# Mode_V1.net
KiCad netlist of a schematic drawn in Altium Designer
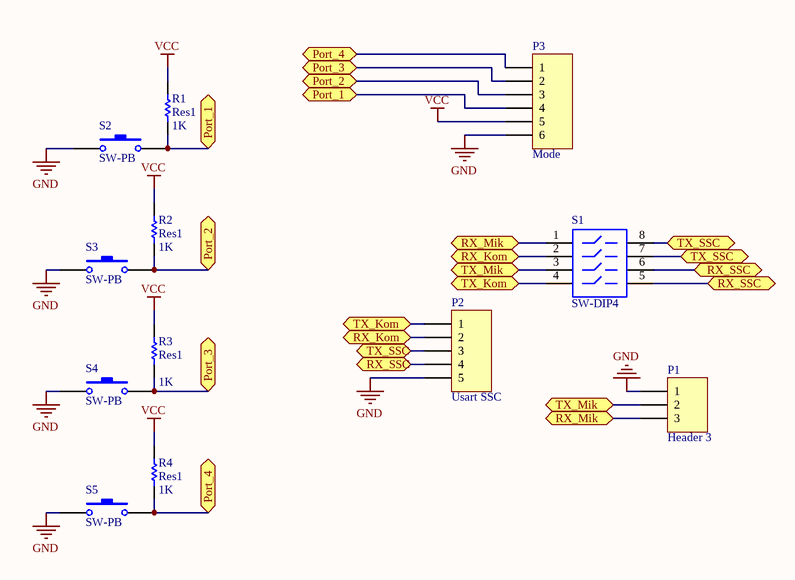
[diagram p0: Mode_V1.SchDoc]

(export (version "E")
  (design (tool "Eeschema 10.0.6"))
  (components
    (comp (ref "P1")
      (value "Header 3")
      (footprint "HDR1X3")
      (description "Header, 3-Pin")
      (fields (field (name "PUBLISHER") "Altium Limited"))
      (libsource (lib "Miscellaneous Connectors") (part "Header 3"))
    )
    (comp (ref "P2")
      (value "Usart SSC")
      (footprint "HDR1X5")
      (description "Header, 5-Pin")
      (fields (field (name "PUBLISHER") "Altium Limited"))
      (libsource (lib "Miscellaneous Connectors") (part "Header 5"))
    )
    (comp (ref "P3")
      (value "Mode")
      (footprint "HDR1X6")
      (description "Header, 6-Pin")
      (fields (field (name "PUBLISHER") "Altium Limited"))
      (libsource (lib "Miscellaneous Connectors") (part "Header 6"))
    )
    (comp (ref "R1")
      (value "Res1")
      (footprint "AXIAL-0.3")
      (description "Resistor")
      (fields (field (name "ALTIUM_VALUE") "1K") (field (name "PUBLISHER") "Altium Limited"))
      (libsource (lib "Miscellaneous Devices") (part "Res1"))
    )
    (comp (ref "R2")
      (value "Res1")
      (footprint "AXIAL-0.3")
      (description "Resistor")
      (fields (field (name "ALTIUM_VALUE") "1K") (field (name "PUBLISHER") "Altium Limited"))
      (libsource (lib "Miscellaneous Devices") (part "Res1"))
    )
    (comp (ref "R3")
      (value "Res1")
      (footprint "AXIAL-0.3")
      (description "Resistor")
      (fields (field (name "ALTIUM_VALUE") "1K") (field (name "PUBLISHER") "Altium Limited"))
      (libsource (lib "Miscellaneous Devices") (part "Res1"))
    )
    (comp (ref "R4")
      (value "Res1")
      (footprint "AXIAL-0.3")
      (description "Resistor")
      (fields (field (name "ALTIUM_VALUE") "1K") (field (name "PUBLISHER") "Altium Limited"))
      (libsource (lib "Miscellaneous Devices") (part "Res1"))
    )
    (comp (ref "S1")
      (value "SW-DIP4")
      (footprint "DIP-8")
      (description "DIP Switch")
      (fields (field (name "PUBLISHER") "Altium Limited"))
      (libsource (lib "Miscellaneous Devices") (part "SW-DIP4"))
    )
    (comp (ref "S2")
      (value "SW-PB")
      (footprint "SPST-2")
      (description "Switch")
      (fields (field (name "PUBLISHER") "Altium Limited"))
      (libsource (lib "Miscellaneous Devices") (part "SW-PB"))
    )
    (comp (ref "S3")
      (value "SW-PB")
      (footprint "SPST-2")
      (description "Switch")
      (fields (field (name "PUBLISHER") "Altium Limited"))
      (libsource (lib "Miscellaneous Devices") (part "SW-PB"))
    )
    (comp (ref "S4")
      (value "SW-PB")
      (footprint "SPST-2")
      (description "Switch")
      (fields (field (name "PUBLISHER") "Altium Limited"))
      (libsource (lib "Miscellaneous Devices") (part "SW-PB"))
    )
    (comp (ref "S5")
      (value "SW-PB")
      (footprint "SPST-2")
      (description "Switch")
      (fields (field (name "PUBLISHER") "Altium Limited"))
      (libsource (lib "Miscellaneous Devices") (part "SW-PB"))
    )
  )
  (nets
    (net (code "1") (name "/Port_1") (class "Default")
      (node (ref "P3") (pin "4") (pinfunction "4_4") (pintype "passive"))
      (node (ref "R1") (pin "1") (pinfunction "1_1") (pintype "passive"))
      (node (ref "S2") (pin "2") (pinfunction "2_2") (pintype "passive"))
    )
    (net (code "2") (name "/Port_2") (class "Default")
      (node (ref "P3") (pin "3") (pinfunction "3_3") (pintype "passive"))
      (node (ref "R2") (pin "1") (pinfunction "1_1") (pintype "passive"))
      (node (ref "S3") (pin "2") (pinfunction "2_2") (pintype "passive"))
    )
    (net (code "3") (name "/Port_3") (class "Default")
      (node (ref "P3") (pin "2") (pinfunction "2_2") (pintype "passive"))
      (node (ref "R3") (pin "1") (pinfunction "1_1") (pintype "passive"))
      (node (ref "S4") (pin "2") (pinfunction "2_2") (pintype "passive"))
    )
    (net (code "4") (name "/Port_4") (class "Default")
      (node (ref "P3") (pin "1") (pinfunction "1_1") (pintype "passive"))
      (node (ref "R4") (pin "1") (pinfunction "1_1") (pintype "passive"))
      (node (ref "S5") (pin "2") (pinfunction "2_2") (pintype "passive"))
    )
    (net (code "5") (name "/RX_Kom") (class "Default")
      (node (ref "P2") (pin "2") (pinfunction "2_2") (pintype "passive"))
      (node (ref "S1") (pin "2") (pinfunction "2_2") (pintype "passive"))
    )
    (net (code "6") (name "/RX_Mik") (class "Default")
      (node (ref "P1") (pin "3") (pinfunction "3_3") (pintype "passive"))
      (node (ref "S1") (pin "1") (pinfunction "1_1") (pintype "passive"))
    )
    (net (code "7") (name "/RX_SSC") (class "Default")
      (node (ref "P2") (pin "4") (pinfunction "4_4") (pintype "passive"))
      (node (ref "S1") (pin "5") (pinfunction "5_5") (pintype "passive"))
      (node (ref "S1") (pin "6") (pinfunction "6_6") (pintype "passive"))
    )
    (net (code "8") (name "/TX_Kom") (class "Default")
      (node (ref "P2") (pin "1") (pinfunction "1_1") (pintype "passive"))
      (node (ref "S1") (pin "4") (pinfunction "4_4") (pintype "passive"))
    )
    (net (code "9") (name "/TX_Mik") (class "Default")
      (node (ref "P1") (pin "2") (pinfunction "2_2") (pintype "passive"))
      (node (ref "S1") (pin "3") (pinfunction "3_3") (pintype "passive"))
    )
    (net (code "10") (name "/TX_SSC") (class "Default")
      (node (ref "P2") (pin "3") (pinfunction "3_3") (pintype "passive"))
      (node (ref "S1") (pin "7") (pinfunction "7_7") (pintype "passive"))
      (node (ref "S1") (pin "8") (pinfunction "8_8") (pintype "passive"))
    )
    (net (code "11") (name "GND") (class "Default")
      (node (ref "P1") (pin "1") (pinfunction "1_1") (pintype "passive"))
      (node (ref "P2") (pin "5") (pinfunction "5_5") (pintype "passive"))
      (node (ref "P3") (pin "6") (pinfunction "6_6") (pintype "passive"))
      (node (ref "S2") (pin "1") (pinfunction "1_1") (pintype "passive"))
      (node (ref "S3") (pin "1") (pinfunction "1_1") (pintype "passive"))
      (node (ref "S4") (pin "1") (pinfunction "1_1") (pintype "passive"))
      (node (ref "S5") (pin "1") (pinfunction "1_1") (pintype "passive"))
    )
    (net (code "12") (name "VCC") (class "Default")
      (node (ref "P3") (pin "5") (pinfunction "5_5") (pintype "passive"))
      (node (ref "R1") (pin "2") (pinfunction "2_2") (pintype "passive"))
      (node (ref "R2") (pin "2") (pinfunction "2_2") (pintype "passive"))
      (node (ref "R3") (pin "2") (pinfunction "2_2") (pintype "passive"))
      (node (ref "R4") (pin "2") (pinfunction "2_2") (pintype "passive"))
    )
  )
)
